# Adafruit_Metro_ESP32-S3_Rev_B.net
KiCad netlist of a schematic drawn in EAGLE
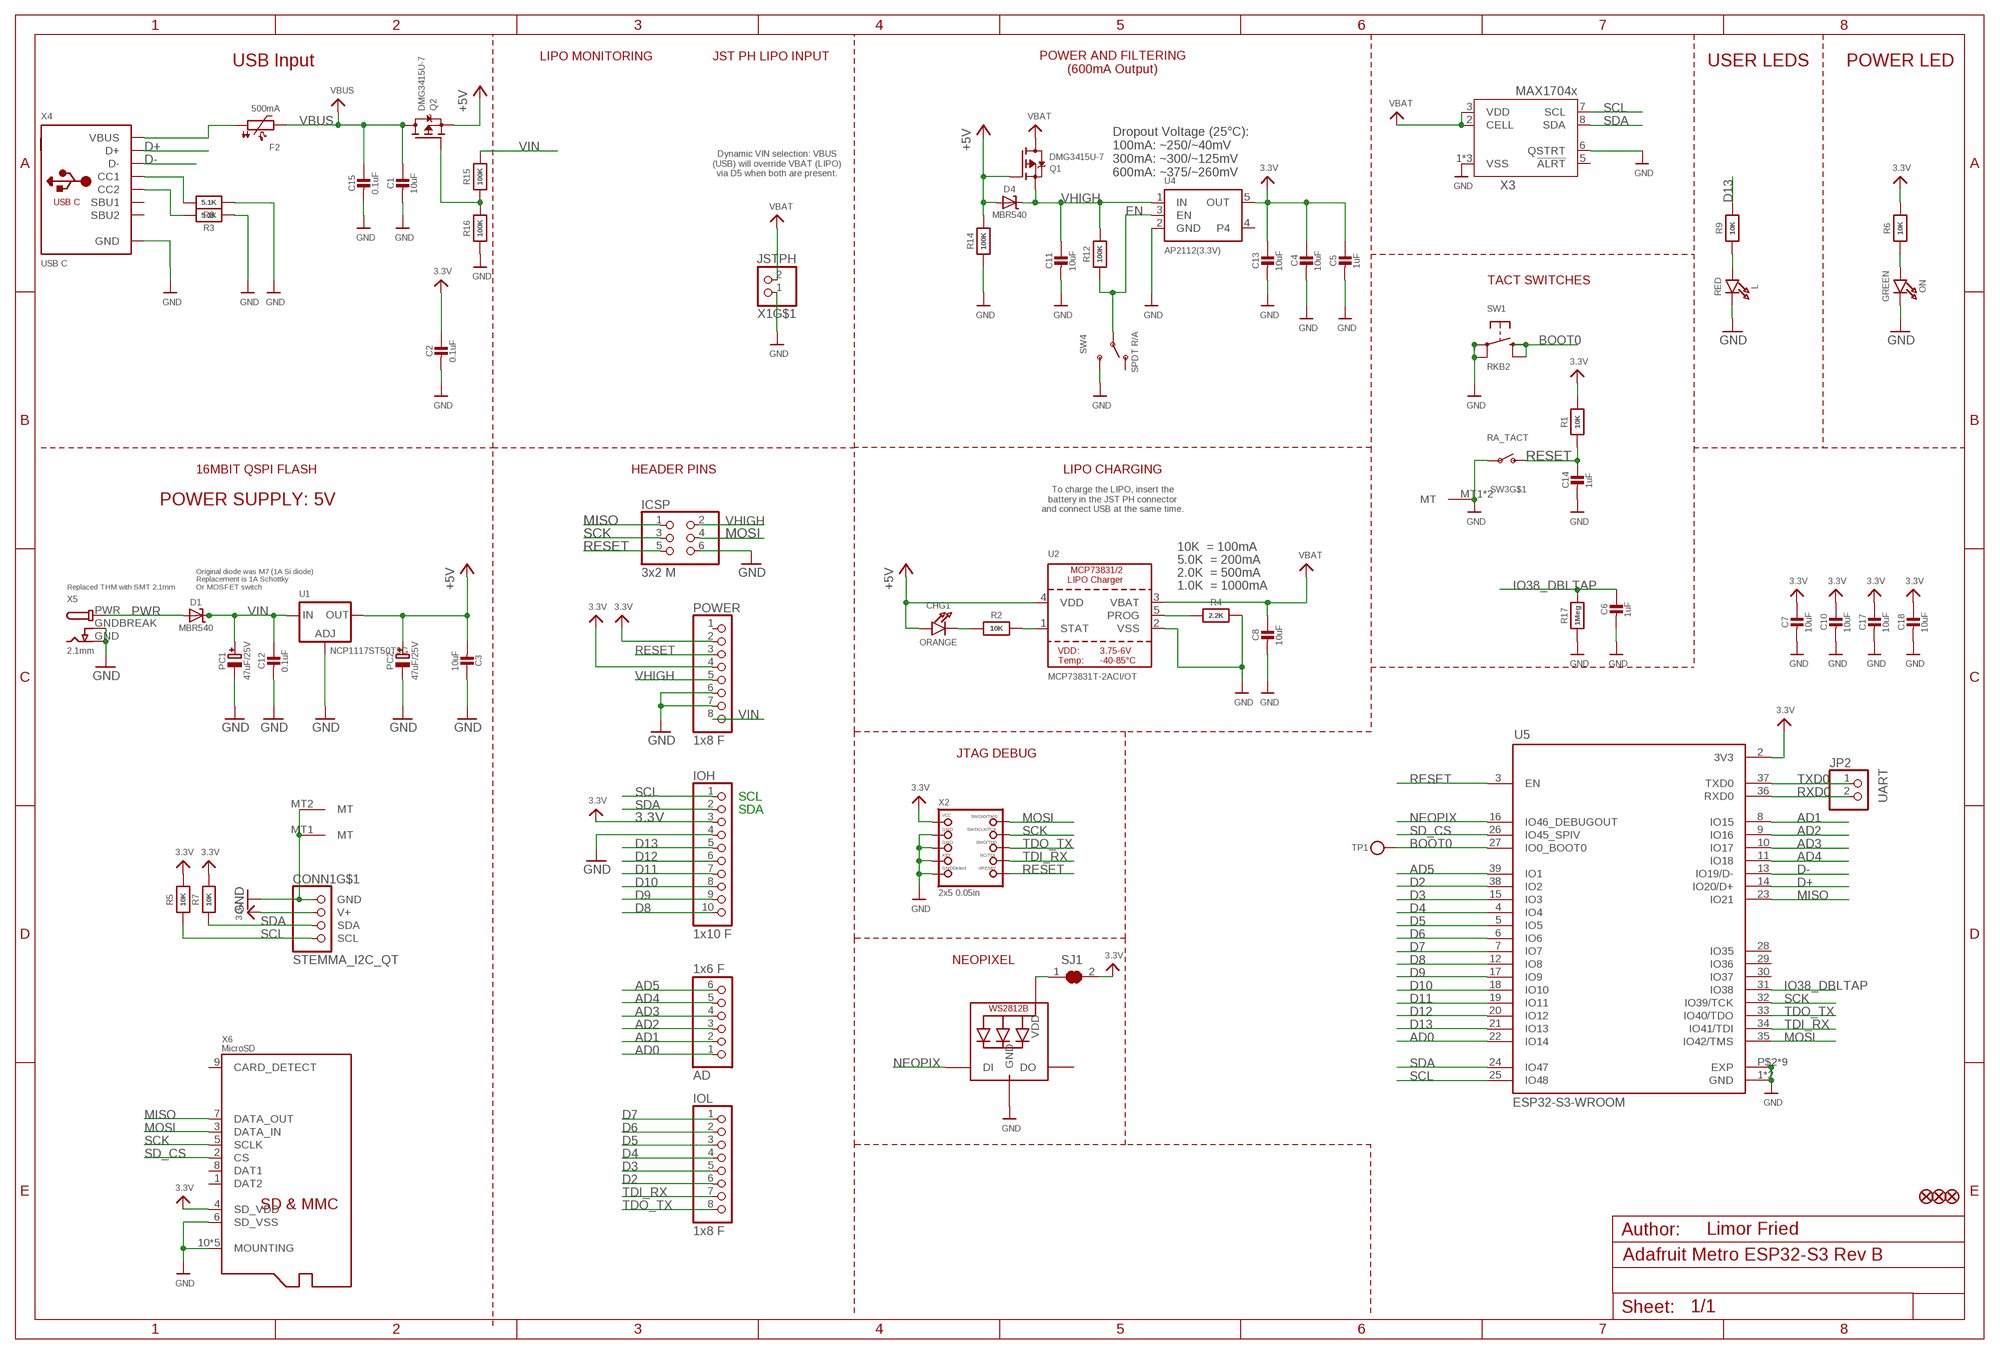
[diagram p0: schematic, sheet 1]

(export (version "E")
  (design (tool "Eeschema 10.0.6"))
  (components
    (comp (ref "AD")
      (value "1x6 F")
      (footprint "eagle-import:1X06_OVALWAVE")
      (libsource (lib "eagle-import") (part "HEADER-1X6OVALWAVE"))
    )
    (comp (ref "C1")
      (value "10uF")
      (footprint "eagle-import:0805-NO")
      (libsource (lib "eagle-import") (part "CAP_CERAMIC0805-NOOUTLINE"))
    )
    (comp (ref "C2")
      (value "0.1uF")
      (footprint "eagle-import:0603-NO")
      (libsource (lib "eagle-import") (part "CAP_CERAMIC0603_NO"))
    )
    (comp (ref "C3")
      (value "10uF")
      (footprint "eagle-import:0805-NO")
      (libsource (lib "eagle-import") (part "CAP_CERAMIC0805-NOOUTLINE"))
    )
    (comp (ref "C4")
      (value "10uF")
      (footprint "eagle-import:0805-NO")
      (libsource (lib "eagle-import") (part "CAP_CERAMIC0805-NOOUTLINE"))
    )
    (comp (ref "C5")
      (value "1uF")
      (footprint "eagle-import:0603-NO")
      (libsource (lib "eagle-import") (part "CAP_CERAMIC0603_NO"))
    )
    (comp (ref "C6")
      (value "1uF")
      (footprint "eagle-import:0603-NO")
      (libsource (lib "eagle-import") (part "CAP_CERAMIC0603_NO"))
    )
    (comp (ref "C7")
      (value "10uF")
      (footprint "eagle-import:0805-NO")
      (libsource (lib "eagle-import") (part "CAP_CERAMIC0805-NOOUTLINE"))
    )
    (comp (ref "C8")
      (value "10uF")
      (footprint "eagle-import:0805-NO")
      (libsource (lib "eagle-import") (part "CAP_CERAMIC0805-NOOUTLINE"))
    )
    (comp (ref "C10")
      (value "10uF")
      (footprint "eagle-import:0805-NO")
      (libsource (lib "eagle-import") (part "CAP_CERAMIC0805-NOOUTLINE"))
    )
    (comp (ref "C11")
      (value "10uF")
      (footprint "eagle-import:0805-NO")
      (libsource (lib "eagle-import") (part "CAP_CERAMIC0805-NOOUTLINE"))
    )
    (comp (ref "C12")
      (value "0.1uF")
      (footprint "eagle-import:0603-NO")
      (libsource (lib "eagle-import") (part "CAP_CERAMIC0603_NO"))
    )
    (comp (ref "C13")
      (value "10uF")
      (footprint "eagle-import:0805-NO")
      (libsource (lib "eagle-import") (part "CAP_CERAMIC0805-NOOUTLINE"))
    )
    (comp (ref "C14")
      (value "1uF")
      (footprint "eagle-import:0603-NO")
      (libsource (lib "eagle-import") (part "CAP_CERAMIC0603_NO"))
    )
    (comp (ref "C15")
      (value "0.1uF")
      (footprint "eagle-import:0603-NO")
      (libsource (lib "eagle-import") (part "CAP_CERAMIC0603_NO"))
    )
    (comp (ref "C17")
      (value "10uF")
      (footprint "eagle-import:0805-NO")
      (libsource (lib "eagle-import") (part "CAP_CERAMIC0805-NOOUTLINE"))
    )
    (comp (ref "C18")
      (value "10uF")
      (footprint "eagle-import:0805-NO")
      (libsource (lib "eagle-import") (part "CAP_CERAMIC0805-NOOUTLINE"))
    )
    (comp (ref "CHG1")
      (value "ORANGE")
      (footprint "eagle-import:CHIPLED_0603_NOOUTLINE")
      (libsource (lib "eagle-import") (part "LED0603_NOOUTLINE"))
    )
    (comp (ref "CONN1")
      (value "STEMMA_I2C_QT")
      (footprint "eagle-import:JST_SH4")
      (libsource (lib "eagle-import") (part "STEMMA_I2C_QT"))
    )
    (comp (ref "D1")
      (value "MBR540")
      (footprint "eagle-import:SOD-123")
      (libsource (lib "eagle-import") (part "DIODE-SCHOTTKYSOD-123"))
    )
    (comp (ref "D4")
      (value "MBR540")
      (footprint "eagle-import:SOD-123")
      (libsource (lib "eagle-import") (part "DIODE-SCHOTTKYSOD-123"))
    )
    (comp (ref "F2")
      (value "500mA")
      (footprint "eagle-import:0805-NO")
      (libsource (lib "eagle-import") (part "PTC_0805"))
    )
    (comp (ref "FD1")
      (value "FIDUCIAL_1MM")
      (footprint "eagle-import:FIDUCIAL_1MM")
      (libsource (lib "eagle-import") (part "FIDUCIAL_1MM"))
    )
    (comp (ref "FD2")
      (value "FIDUCIAL_1MM")
      (footprint "eagle-import:FIDUCIAL_1MM")
      (libsource (lib "eagle-import") (part "FIDUCIAL_1MM"))
    )
    (comp (ref "FD3")
      (value "FIDUCIAL_1MM")
      (footprint "eagle-import:FIDUCIAL_1MM")
      (libsource (lib "eagle-import") (part "FIDUCIAL_1MM"))
    )
    (comp (ref "ICSP")
      (value "3x2 M")
      (footprint "eagle-import:2X03_ROUND_70MIL")
      (libsource (lib "eagle-import") (part "HEADER-2X3"))
    )
    (comp (ref "IOH")
      (value "1x10 F")
      (footprint "eagle-import:1X10_OVALWAVE")
      (libsource (lib "eagle-import") (part "HEADER-1X10OVALWAVE"))
    )
    (comp (ref "IOL")
      (value "1x8 F")
      (footprint "eagle-import:1X08_OVALWAVE")
      (libsource (lib "eagle-import") (part "HEADER-1X8OVALWAVE"))
    )
    (comp (ref "JP2")
      (value "UART")
      (footprint "eagle-import:1X02_ROUND")
      (libsource (lib "eagle-import") (part "HEADER-1X2ROUND"))
    )
    (comp (ref "L")
      (value "RED")
      (footprint "eagle-import:CHIPLED_0603_NOOUTLINE")
      (libsource (lib "eagle-import") (part "LED0603_NOOUTLINE"))
    )
    (comp (ref "LED1")
      (value "WS2812B_3535FULL")
      (footprint "eagle-import:LED3535_FULLPADS")
      (libsource (lib "eagle-import") (part "WS2812B_3535FULL"))
    )
    (comp (ref "ON")
      (value "GREEN")
      (footprint "eagle-import:CHIPLED_0603_NOOUTLINE")
      (libsource (lib "eagle-import") (part "LED0603_NOOUTLINE"))
    )
    (comp (ref "PC1")
      (value "47uF/25V")
      (footprint "eagle-import:PANASONIC_D")
      (libsource (lib "eagle-import") (part "CAP_ELECTROLYTICPANASONIC_D"))
    )
    (comp (ref "PC2")
      (value "47uF/25V")
      (footprint "eagle-import:PANASONIC_D")
      (libsource (lib "eagle-import") (part "CAP_ELECTROLYTICPANASONIC_D"))
    )
    (comp (ref "POWER")
      (value "1x8 F")
      (footprint "eagle-import:1X08_OVALWAVE")
      (libsource (lib "eagle-import") (part "HEADER-1X8OVALWAVE"))
    )
    (comp (ref "Q1")
      (value "DMG3415U-7")
      (footprint "eagle-import:SOT23-R")
      (libsource (lib "eagle-import") (part "MOSFET-P"))
    )
    (comp (ref "Q2")
      (value "DMG3415U-7")
      (footprint "eagle-import:SOT23-R")
      (libsource (lib "eagle-import") (part "MOSFET-P"))
    )
    (comp (ref "R1")
      (value "10K")
      (footprint "eagle-import:0603-NO")
      (libsource (lib "eagle-import") (part "RESISTOR_0603_NOOUT"))
    )
    (comp (ref "R2")
      (value "10K")
      (footprint "eagle-import:0603-NO")
      (libsource (lib "eagle-import") (part "RESISTOR_0603_NOOUT"))
    )
    (comp (ref "R3")
      (value "5.1K")
      (footprint "eagle-import:0603-NO")
      (libsource (lib "eagle-import") (part "RESISTOR_0603_NOOUT"))
    )
    (comp (ref "R4")
      (value "2.2K")
      (footprint "eagle-import:0603-NO")
      (libsource (lib "eagle-import") (part "RESISTOR_0603_NOOUT"))
    )
    (comp (ref "R5")
      (value "10K")
      (footprint "eagle-import:0603-NO")
      (libsource (lib "eagle-import") (part "RESISTOR_0603_NOOUT"))
    )
    (comp (ref "R6")
      (value "10K")
      (footprint "eagle-import:0603-NO")
      (libsource (lib "eagle-import") (part "RESISTOR_0603_NOOUT"))
    )
    (comp (ref "R7")
      (value "10K")
      (footprint "eagle-import:0603-NO")
      (libsource (lib "eagle-import") (part "RESISTOR_0603_NOOUT"))
    )
    (comp (ref "R8")
      (value "5.1K")
      (footprint "eagle-import:0603-NO")
      (libsource (lib "eagle-import") (part "RESISTOR_0603_NOOUT"))
    )
    (comp (ref "R9")
      (value "10K")
      (footprint "eagle-import:0603-NO")
      (libsource (lib "eagle-import") (part "RESISTOR_0603_NOOUT"))
    )
    (comp (ref "R12")
      (value "100K")
      (footprint "eagle-import:0603-NO")
      (libsource (lib "eagle-import") (part "RESISTOR_0603_NOOUT"))
    )
    (comp (ref "R14")
      (value "100K")
      (footprint "eagle-import:0603-NO")
      (libsource (lib "eagle-import") (part "RESISTOR_0603_NOOUT"))
    )
    (comp (ref "R15")
      (value "100K")
      (footprint "eagle-import:0603-NO")
      (libsource (lib "eagle-import") (part "RESISTOR_0603_NOOUT"))
    )
    (comp (ref "R16")
      (value "100K")
      (footprint "eagle-import:0603-NO")
      (libsource (lib "eagle-import") (part "RESISTOR_0603_NOOUT"))
    )
    (comp (ref "R17")
      (value "1Meg")
      (footprint "eagle-import:0603-NO")
      (libsource (lib "eagle-import") (part "RESISTOR_0603_NOOUT"))
    )
    (comp (ref "SJ1")
      (value "SOLDERJUMPER_CLOSED")
      (footprint "eagle-import:SOLDERJUMPER_CLOSEDWIRE")
      (libsource (lib "eagle-import") (part "SOLDERJUMPER_CLOSED"))
    )
    (comp (ref "SW1")
      (value "RKB2")
      (footprint "eagle-import:BTN_RKB2_4.6X2.8")
      (libsource (lib "eagle-import") (part "SWITCH_TACT_SMT_RKB2"))
    )
    (comp (ref "SW3")
      (value "RA_TACT")
      (footprint "eagle-import:SPST_TACTILE_RA")
      (libsource (lib "eagle-import") (part "SWITCH_SPST_MNT_TACT_RA"))
    )
    (comp (ref "SW4")
      (value "SPDT R/A")
      (footprint "eagle-import:SPDT_SMT_SSSS811101")
      (libsource (lib "eagle-import") (part "SWITCH_SPDT"))
    )
    (comp (ref "TP1")
      (value "TESTPOINTROUND1.5MMNO")
      (footprint "eagle-import:TESTPOINT_ROUND_1.5MM_NO")
      (libsource (lib "eagle-import") (part "TESTPOINTROUND1.5MMNO"))
    )
    (comp (ref "U1")
      (value "NCP1117ST50T3G")
      (footprint "eagle-import:SOT223-R")
      (libsource (lib "eagle-import") (part "LM1117SOT223-REFLOW"))
    )
    (comp (ref "U2")
      (value "MCP73831T-2ACI/OT")
      (footprint "eagle-import:SOT23-5")
      (libsource (lib "eagle-import") (part "MCP73831/2"))
    )
    (comp (ref "U4")
      (value "AP2112(3.3V)")
      (footprint "eagle-import:SOT23-5")
      (fields (field (name "JLC_ROTATION") "0"))
      (libsource (lib "eagle-import") (part "VREG_SOT23-5"))
    )
    (comp (ref "U5")
      (value "ESP32-S3-WROOM")
      (footprint "eagle-import:S3-WROOM32")
      (libsource (lib "eagle-import") (part "ESP32-S3-WROOM"))
    )
    (comp (ref "X1")
      (value "JSTPH")
      (footprint "eagle-import:JSTPH2_BATT")
      (libsource (lib "eagle-import") (part "CON_JST_PH_2PIN_MT_BATT"))
    )
    (comp (ref "X2")
      (value "2x5 0.05in")
      (footprint "eagle-import:2X05_1.27MM_BOX_POSTS")
      (libsource (lib "eagle-import") (part "JTAG-CORTEXBOXPOSTS"))
    )
    (comp (ref "X3")
      (value "MAX17048/T")
      (footprint "eagle-import:TDFN8_2X2MM")
      (libsource (lib "eagle-import") (part "MAX17048/T"))
    )
    (comp (ref "X4")
      (value "USB C")
      (footprint "eagle-import:USB_C_CUSB31-CFM2AX-01-X")
      (libsource (lib "eagle-import") (part "USB_C"))
    )
    (comp (ref "X5")
      (value "2.1mm")
      (footprint "eagle-import:DCJACK_2MM_PTH")
      (libsource (lib "eagle-import") (part "DCBARRELPTH"))
    )
    (comp (ref "X6")
      (value "MicroSD")
      (footprint "eagle-import:MOLEX_104031-0811")
      (libsource (lib "eagle-import") (part "MICROSD104031-0811"))
    )
  )
  (nets
    (net (code "1") (name "+5V") (class "Default")
      (node (ref "C3") (pin "2") (pinfunction "2_2") (pintype "passive"))
      (node (ref "CHG1") (pin "A") (pinfunction "A_A") (pintype "passive"))
      (node (ref "D4") (pin "A") (pinfunction "A_A") (pintype "passive"))
      (node (ref "PC2") (pin "+") (pinfunction "+_+") (pintype "passive"))
      (node (ref "Q1") (pin "1") (pinfunction "G_1") (pintype "passive"))
      (node (ref "Q2") (pin "2") (pinfunction "S_2") (pintype "passive"))
      (node (ref "R14") (pin "2") (pinfunction "2_2") (pintype "passive"))
      (node (ref "U1") (pin "2") (pinfunction "OUT_2") (pintype "passive"))
      (node (ref "U1") (pin "4") (pinfunction "OUT_4") (pintype "passive"))
      (node (ref "U2") (pin "4") (pinfunction "VDD_4") (pintype "power_in"))
    )
    (net (code "2") (name "/AD0") (class "Default")
      (node (ref "AD") (pin "1") (pinfunction "1_1") (pintype "passive"))
      (node (ref "U5") (pin "22") (pinfunction "IO14_22") (pintype "bidirectional"))
    )
    (net (code "3") (name "/AD1") (class "Default")
      (node (ref "AD") (pin "2") (pinfunction "2_2") (pintype "passive"))
      (node (ref "U5") (pin "8") (pinfunction "IO15_8") (pintype "bidirectional"))
    )
    (net (code "4") (name "/AD2") (class "Default")
      (node (ref "AD") (pin "3") (pinfunction "3_3") (pintype "passive"))
      (node (ref "U5") (pin "9") (pinfunction "IO16_9") (pintype "bidirectional"))
    )
    (net (code "5") (name "/AD3") (class "Default")
      (node (ref "AD") (pin "4") (pinfunction "4_4") (pintype "passive"))
      (node (ref "U5") (pin "10") (pinfunction "IO17_10") (pintype "bidirectional"))
    )
    (net (code "6") (name "/AD4") (class "Default")
      (node (ref "AD") (pin "5") (pinfunction "5_5") (pintype "passive"))
      (node (ref "U5") (pin "11") (pinfunction "IO18_11") (pintype "bidirectional"))
    )
    (net (code "7") (name "/AD5") (class "Default")
      (node (ref "AD") (pin "6") (pinfunction "6_6") (pintype "passive"))
      (node (ref "U5") (pin "39") (pinfunction "IO1_39") (pintype "bidirectional"))
    )
    (net (code "8") (name "/BOOT0") (class "Default")
      (node (ref "SW1") (pin "B") (pinfunction "S_B") (pintype "passive"))
      (node (ref "SW1") (pin "B'") (pinfunction "S1_B'") (pintype "passive"))
      (node (ref "TP1") (pin "P$1") (pinfunction "P$1_P$1") (pintype "bidirectional"))
      (node (ref "U5") (pin "27") (pinfunction "IO0_BOOT0_27") (pintype "bidirectional"))
    )
    (net (code "9") (name "/D+") (class "Default")
      (node (ref "U5") (pin "14") (pinfunction "IO20/D+_14") (pintype "bidirectional"))
      (node (ref "X4") (pin "A6") (pinfunction "D+_A6") (pintype "bidirectional"))
      (node (ref "X4") (pin "B6") (pinfunction "D+_B6") (pintype "bidirectional"))
    )
    (net (code "10") (name "/D-") (class "Default")
      (node (ref "U5") (pin "13") (pinfunction "IO19/D-_13") (pintype "bidirectional"))
      (node (ref "X4") (pin "A7") (pinfunction "D-_A7") (pintype "bidirectional"))
      (node (ref "X4") (pin "B7") (pinfunction "D-_B7") (pintype "bidirectional"))
    )
    (net (code "11") (name "/D2") (class "Default")
      (node (ref "IOL") (pin "6") (pinfunction "6_6") (pintype "passive"))
      (node (ref "U5") (pin "38") (pinfunction "IO2_38") (pintype "bidirectional"))
    )
    (net (code "12") (name "/D3") (class "Default")
      (node (ref "IOL") (pin "5") (pinfunction "5_5") (pintype "passive"))
      (node (ref "U5") (pin "15") (pinfunction "IO3_15") (pintype "bidirectional"))
    )
    (net (code "13") (name "/D4") (class "Default")
      (node (ref "IOL") (pin "4") (pinfunction "4_4") (pintype "passive"))
      (node (ref "U5") (pin "4") (pinfunction "IO4_4") (pintype "bidirectional"))
    )
    (net (code "14") (name "/D5") (class "Default")
      (node (ref "IOL") (pin "3") (pinfunction "3_3") (pintype "passive"))
      (node (ref "U5") (pin "5") (pinfunction "IO5_5") (pintype "bidirectional"))
    )
    (net (code "15") (name "/D6") (class "Default")
      (node (ref "IOL") (pin "2") (pinfunction "2_2") (pintype "passive"))
      (node (ref "U5") (pin "6") (pinfunction "IO6_6") (pintype "bidirectional"))
    )
    (net (code "16") (name "/D7") (class "Default")
      (node (ref "IOL") (pin "1") (pinfunction "1_1") (pintype "passive"))
      (node (ref "U5") (pin "7") (pinfunction "IO7_7") (pintype "bidirectional"))
    )
    (net (code "17") (name "/D8") (class "Default")
      (node (ref "IOH") (pin "10") (pinfunction "10_10") (pintype "passive"))
      (node (ref "U5") (pin "12") (pinfunction "IO8_12") (pintype "bidirectional"))
    )
    (net (code "18") (name "/D9") (class "Default")
      (node (ref "IOH") (pin "9") (pinfunction "9_9") (pintype "passive"))
      (node (ref "U5") (pin "17") (pinfunction "IO9_17") (pintype "bidirectional"))
    )
    (net (code "19") (name "/D10") (class "Default")
      (node (ref "IOH") (pin "8") (pinfunction "8_8") (pintype "passive"))
      (node (ref "U5") (pin "18") (pinfunction "IO10_18") (pintype "bidirectional"))
    )
    (net (code "20") (name "/D11") (class "Default")
      (node (ref "IOH") (pin "7") (pinfunction "7_7") (pintype "passive"))
      (node (ref "U5") (pin "19") (pinfunction "IO11_19") (pintype "bidirectional"))
    )
    (net (code "21") (name "/D12") (class "Default")
      (node (ref "IOH") (pin "6") (pinfunction "6_6") (pintype "passive"))
      (node (ref "U5") (pin "20") (pinfunction "IO12_20") (pintype "bidirectional"))
    )
    (net (code "22") (name "/D13") (class "Default")
      (node (ref "IOH") (pin "5") (pinfunction "5_5") (pintype "passive"))
      (node (ref "R9") (pin "2") (pinfunction "2_2") (pintype "passive"))
      (node (ref "U5") (pin "21") (pinfunction "IO13_21") (pintype "bidirectional"))
    )
    (net (code "23") (name "/EN") (class "Default")
      (node (ref "R12") (pin "1") (pinfunction "1_1") (pintype "passive"))
      (node (ref "SW4") (pin "B") (pinfunction "P_B") (pintype "passive"))
      (node (ref "U4") (pin "3") (pinfunction "EN_3") (pintype "input"))
    )
    (net (code "24") (name "/IO38_DBLTAP") (class "Default")
      (node (ref "C6") (pin "1") (pinfunction "1_1") (pintype "passive"))
      (node (ref "R17") (pin "2") (pinfunction "2_2") (pintype "passive"))
      (node (ref "U5") (pin "31") (pinfunction "IO38_31") (pintype "bidirectional"))
    )
    (net (code "25") (name "/MISO") (class "Default")
      (node (ref "ICSP") (pin "1") (pinfunction "1_1") (pintype "passive"))
      (node (ref "U5") (pin "23") (pinfunction "IO21_23") (pintype "bidirectional"))
      (node (ref "X6") (pin "7") (pinfunction "DATA_OUT_7") (pintype "output"))
    )
    (net (code "26") (name "/MOSI") (class "Default")
      (node (ref "ICSP") (pin "4") (pinfunction "4_4") (pintype "passive"))
      (node (ref "U5") (pin "35") (pinfunction "IO42/TMS_35") (pintype "bidirectional"))
      (node (ref "X2") (pin "2") (pinfunction "SWDIO_2") (pintype "bidirectional"))
      (node (ref "X6") (pin "3") (pinfunction "DATA_IN_3") (pintype "input"))
    )
    (net (code "27") (name "/NEOPIX") (class "Default")
      (node (ref "LED1") (pin "1") (pinfunction "DI_1") (pintype "input"))
      (node (ref "U5") (pin "16") (pinfunction "IO46_DEBUGOUT_16") (pintype "input"))
    )
    (net (code "28") (name "/PWR") (class "Default")
      (node (ref "D1") (pin "A") (pinfunction "A_A") (pintype "passive"))
      (node (ref "X5") (pin "PWR") (pinfunction "PWR_PWR") (pintype "power_in"))
    )
    (net (code "29") (name "/RESET") (class "Default")
      (node (ref "C14") (pin "1") (pinfunction "1_1") (pintype "passive"))
      (node (ref "ICSP") (pin "5") (pinfunction "5_5") (pintype "passive"))
      (node (ref "POWER") (pin "3") (pinfunction "3_3") (pintype "passive"))
      (node (ref "R1") (pin "1") (pinfunction "1_1") (pintype "passive"))
      (node (ref "SW3") (pin "2") (pinfunction "S_2") (pintype "passive"))
      (node (ref "U5") (pin "3") (pinfunction "EN_3") (pintype "input"))
      (node (ref "X2") (pin "10") (pinfunction "NRESET_10") (pintype "bidirectional"))
    )
    (net (code "30") (name "/RXD0") (class "Default")
      (node (ref "JP2") (pin "2") (pinfunction "2_2") (pintype "passive"))
      (node (ref "U5") (pin "36") (pinfunction "RXD0_36") (pintype "bidirectional"))
    )
    (net (code "31") (name "/SCK") (class "Default")
      (node (ref "ICSP") (pin "3") (pinfunction "3_3") (pintype "passive"))
      (node (ref "U5") (pin "32") (pinfunction "IO39/TCK_32") (pintype "bidirectional"))
      (node (ref "X2") (pin "4") (pinfunction "SWDCLK_4") (pintype "bidirectional"))
      (node (ref "X6") (pin "5") (pinfunction "SCLK_5") (pintype "input"))
    )
    (net (code "32") (name "/SCL") (class "Default")
      (node (ref "CONN1") (pin "4") (pinfunction "SCL_4") (pintype "passive"))
      (node (ref "IOH") (pin "1") (pinfunction "1_1") (pintype "passive"))
      (node (ref "R5") (pin "1") (pinfunction "1_1") (pintype "passive"))
      (node (ref "U5") (pin "25") (pinfunction "IO48_25") (pintype "input"))
      (node (ref "X3") (pin "7") (pinfunction "SCL_7") (pintype "bidirectional"))
    )
    (net (code "33") (name "/SDA") (class "Default")
      (node (ref "CONN1") (pin "3") (pinfunction "SDA_3") (pintype "passive"))
      (node (ref "IOH") (pin "2") (pinfunction "2_2") (pintype "passive"))
      (node (ref "R7") (pin "1") (pinfunction "1_1") (pintype "passive"))
      (node (ref "U5") (pin "24") (pinfunction "IO47_24") (pintype "bidirectional"))
      (node (ref "X3") (pin "8") (pinfunction "SDA_8") (pintype "bidirectional"))
    )
    (net (code "34") (name "/SD_CS") (class "Default")
      (node (ref "U5") (pin "26") (pinfunction "IO45_SPIV_26") (pintype "bidirectional"))
      (node (ref "X6") (pin "2") (pinfunction "CS_2") (pintype "input"))
    )
    (net (code "35") (name "/TDI_RX") (class "Default")
      (node (ref "IOL") (pin "7") (pinfunction "7_7") (pintype "passive"))
      (node (ref "U5") (pin "34") (pinfunction "IO41/TDI_34") (pintype "bidirectional"))
      (node (ref "X2") (pin "8") (pinfunction "TDI_8") (pintype "bidirectional"))
    )
    (net (code "36") (name "/TDO_TX") (class "Default")
      (node (ref "IOL") (pin "8") (pinfunction "8_8") (pintype "passive"))
      (node (ref "U5") (pin "33") (pinfunction "IO40/TDO_33") (pintype "bidirectional"))
      (node (ref "X2") (pin "6") (pinfunction "SWO_6") (pintype "bidirectional"))
    )
    (net (code "37") (name "/TXD0") (class "Default")
      (node (ref "JP2") (pin "1") (pinfunction "1_1") (pintype "passive"))
      (node (ref "U5") (pin "37") (pinfunction "TXD0_37") (pintype "bidirectional"))
    )
    (net (code "38") (name "/VHIGH") (class "Default")
      (node (ref "C11") (pin "1") (pinfunction "1_1") (pintype "passive"))
      (node (ref "D4") (pin "C") (pinfunction "C_C") (pintype "passive"))
      (node (ref "ICSP") (pin "2") (pinfunction "2_2") (pintype "passive"))
      (node (ref "POWER") (pin "5") (pinfunction "5_5") (pintype "passive"))
      (node (ref "Q1") (pin "2") (pinfunction "S_2") (pintype "passive"))
      (node (ref "R12") (pin "2") (pinfunction "2_2") (pintype "passive"))
      (node (ref "U4") (pin "1") (pinfunction "IN_1") (pintype "power_in"))
    )
    (net (code "39") (name "/VIN") (class "Default")
      (node (ref "C12") (pin "1") (pinfunction "1_1") (pintype "passive"))
      (node (ref "D1") (pin "C") (pinfunction "C_C") (pintype "passive"))
      (node (ref "PC1") (pin "+") (pinfunction "+_+") (pintype "passive"))
      (node (ref "POWER") (pin "8") (pinfunction "8_8") (pintype "passive"))
      (node (ref "R15") (pin "2") (pinfunction "2_2") (pintype "passive"))
      (node (ref "U1") (pin "3") (pinfunction "IN_3") (pintype "input"))
    )
    (net (code "40") (name "3.3V") (class "Default")
      (node (ref "C10") (pin "1") (pinfunction "1_1") (pintype "passive"))
      (node (ref "C13") (pin "1") (pinfunction "1_1") (pintype "passive"))
      (node (ref "C17") (pin "1") (pinfunction "1_1") (pintype "passive"))
      (node (ref "C18") (pin "1") (pinfunction "1_1") (pintype "passive"))
      (node (ref "C2") (pin "1") (pinfunction "1_1") (pintype "passive"))
      (node (ref "C4") (pin "1") (pinfunction "1_1") (pintype "passive"))
      (node (ref "C5") (pin "1") (pinfunction "1_1") (pintype "passive"))
      (node (ref "C7") (pin "1") (pinfunction "1_1") (pintype "passive"))
      (node (ref "CONN1") (pin "2") (pinfunction "V+_2") (pintype "passive"))
      (node (ref "IOH") (pin "3") (pinfunction "3_3") (pintype "passive"))
      (node (ref "POWER") (pin "2") (pinfunction "2_2") (pintype "passive"))
      (node (ref "POWER") (pin "4") (pinfunction "4_4") (pintype "passive"))
      (node (ref "R1") (pin "2") (pinfunction "2_2") (pintype "passive"))
      (node (ref "R5") (pin "2") (pinfunction "2_2") (pintype "passive"))
      (node (ref "R6") (pin "2") (pinfunction "2_2") (pintype "passive"))
      (node (ref "R7") (pin "2") (pinfunction "2_2") (pintype "passive"))
      (node (ref "SJ1") (pin "2") (pinfunction "2_2") (pintype "passive"))
      (node (ref "U4") (pin "5") (pinfunction "OUT_5") (pintype "power_in"))
      (node (ref "U5") (pin "2") (pinfunction "3V3_2") (pintype "power_in"))
      (node (ref "X2") (pin "1") (pinfunction "VCC_1") (pintype "power_in"))
      (node (ref "X6") (pin "4") (pinfunction "SD_VDD_4") (pintype "power_in"))
    )
    (net (code "41") (name "GND") (class "Default")
      (node (ref "C1") (pin "2") (pinfunction "2_2") (pintype "passive"))
      (node (ref "C10") (pin "2") (pinfunction "2_2") (pintype "passive"))
      (node (ref "C11") (pin "2") (pinfunction "2_2") (pintype "passive"))
      (node (ref "C12") (pin "2") (pinfunction "2_2") (pintype "passive"))
      (node (ref "C13") (pin "2") (pinfunction "2_2") (pintype "passive"))
      (node (ref "C14") (pin "2") (pinfunction "2_2") (pintype "passive"))
      (node (ref "C15") (pin "2") (pinfunction "2_2") (pintype "passive"))
      (node (ref "C17") (pin "2") (pinfunction "2_2") (pintype "passive"))
      (node (ref "C18") (pin "2") (pinfunction "2_2") (pintype "passive"))
      (node (ref "C2") (pin "2") (pinfunction "2_2") (pintype "passive"))
      (node (ref "C3") (pin "1") (pinfunction "1_1") (pintype "passive"))
      (node (ref "C4") (pin "2") (pinfunction "2_2") (pintype "passive"))
      (node (ref "C5") (pin "2") (pinfunction "2_2") (pintype "passive"))
      (node (ref "C6") (pin "2") (pinfunction "2_2") (pintype "passive"))
      (node (ref "C7") (pin "2") (pinfunction "2_2") (pintype "passive"))
      (node (ref "C8") (pin "2") (pinfunction "2_2") (pintype "passive"))
      (node (ref "CONN1") (pin "1") (pinfunction "GND_1") (pintype "passive"))
      (node (ref "CONN1") (pin "MT1") (pinfunction "MT_MT1") (pintype "bidirectional"))
      (node (ref "CONN1") (pin "MT2") (pinfunction "MT_MT2") (pintype "bidirectional"))
      (node (ref "ICSP") (pin "6") (pinfunction "6_6") (pintype "passive"))
      (node (ref "IOH") (pin "4") (pinfunction "4_4") (pintype "passive"))
      (node (ref "L") (pin "C") (pinfunction "C_C") (pintype "passive"))
      (node (ref "LED1") (pin "4") (pinfunction "GND_4") (pintype "power_in"))
      (node (ref "ON") (pin "C") (pinfunction "C_C") (pintype "passive"))
      (node (ref "PC1") (pin "-") (pinfunction "-_-") (pintype "passive"))
      (node (ref "PC2") (pin "-") (pinfunction "-_-") (pintype "passive"))
      (node (ref "POWER") (pin "6") (pinfunction "6_6") (pintype "passive"))
      (node (ref "POWER") (pin "7") (pinfunction "7_7") (pintype "passive"))
      (node (ref "R14") (pin "1") (pinfunction "1_1") (pintype "passive"))
      (node (ref "R16") (pin "1") (pinfunction "1_1") (pintype "passive"))
      (node (ref "R17") (pin "1") (pinfunction "1_1") (pintype "passive"))
      (node (ref "R3") (pin "1") (pinfunction "1_1") (pintype "passive"))
      (node (ref "R4") (pin "2") (pinfunction "2_2") (pintype "passive"))
      (node (ref "R8") (pin "1") (pinfunction "1_1") (pintype "passive"))
      (node (ref "SW1") (pin "A") (pinfunction "P_A") (pintype "passive"))
      (node (ref "SW1") (pin "A'") (pinfunction "P1_A'") (pintype "passive"))
      (node (ref "SW3") (pin "1") (pinfunction "P_1") (pintype "passive"))
      (node (ref "SW3") (pin "MT1") (pinfunction "MT_MT1") (pintype "bidirectional"))
      (node (ref "SW3") (pin "MT2") (pinfunction "MT_MT2") (pintype "bidirectional"))
      (node (ref "SW4") (pin "C") (pinfunction "S_C") (pintype "passive"))
      (node (ref "U1") (pin "1") (pinfunction "ADJ_1") (pintype "input"))
      (node (ref "U2") (pin "2") (pinfunction "VSS_2") (pintype "power_in"))
      (node (ref "U4") (pin "2") (pinfunction "GND_2") (pintype "power_in"))
      (node (ref "U5") (pin "1") (pinfunction "GND_1") (pintype "power_in"))
      (node (ref "U5") (pin "40") (pinfunction "GND_40") (pintype "power_in"))
      (node (ref "U5") (pin "P$10") (pinfunction "EXP_P$10") (pintype "power_in"))
      (node (ref "U5") (pin "P$2") (pinfunction "EXP_P$2") (pintype "power_in"))
      (node (ref "U5") (pin "P$3") (pinfunction "EXP_P$3") (pintype "power_in"))
      (node (ref "U5") (pin "P$4") (pinfunction "EXP_P$4") (pintype "power_in"))
      (node (ref "U5") (pin "P$5") (pinfunction "EXP_P$5") (pintype "power_in"))
      (node (ref "U5") (pin "P$6") (pinfunction "EXP_P$6") (pintype "power_in"))
      (node (ref "U5") (pin "P$7") (pinfunction "EXP_P$7") (pintype "power_in"))
      (node (ref "U5") (pin "P$8") (pinfunction "EXP_P$8") (pintype "power_in"))
      (node (ref "U5") (pin "P$9") (pinfunction "EXP_P$9") (pintype "power_in"))
      (node (ref "X1") (pin "1") (pinfunction "1_1") (pintype "passive"))
      (node (ref "X2") (pin "3") (pinfunction "GND_3") (pintype "power_in"))
      (node (ref "X2") (pin "5") (pinfunction "GND_5") (pintype "power_in"))
      (node (ref "X2") (pin "7") (pinfunction "KEY_7") (pintype "bidirectional"))
      (node (ref "X2") (pin "9") (pinfunction "GNDDETECT_9") (pintype "bidirectional"))
      (node (ref "X3") (pin "1") (pinfunction "VSS_1") (pintype "power_in"))
      (node (ref "X3") (pin "4") (pinfunction "VSS_4") (pintype "power_in"))
      (node (ref "X3") (pin "6") (pinfunction "QSTRT_6") (pintype "input"))
      (node (ref "X3") (pin "THERMAL") (pinfunction "VSS_THERMAL") (pintype "power_in"))
      (node (ref "X4") (pin "A1B12") (pinfunction "GND_A1B12") (pintype "power_in"))
      (node (ref "X4") (pin "B1A12") (pinfunction "GND_B1A12") (pintype "power_in"))
      (node (ref "X5") (pin "GND") (pinfunction "GND_GND") (pintype "power_in"))
      (node (ref "X5") (pin "GNDBREAK") (pinfunction "GNDBREAK_GNDBREAK") (pintype "power_in"))
      (node (ref "X6") (pin "10") (pinfunction "MOUNTING_10") (pintype "passive"))
      (node (ref "X6") (pin "6") (pinfunction "SD_VSS_6") (pintype "power_in"))
      (node (ref "X6") (pin "G1") (pinfunction "MOUNTING_G1") (pintype "passive"))
      (node (ref "X6") (pin "G2") (pinfunction "MOUNTING_G2") (pintype "passive"))
      (node (ref "X6") (pin "G3") (pinfunction "MOUNTING_G3") (pintype "passive"))
      (node (ref "X6") (pin "G4") (pinfunction "MOUNTING_G4") (pintype "passive"))
    )
    (net (code "42") (name "Net-(CHG1-PadC)") (class "Default")
      (node (ref "CHG1") (pin "C") (pinfunction "C_C") (pintype "passive"))
      (node (ref "R2") (pin "1") (pinfunction "1_1") (pintype "passive"))
    )
    (net (code "43") (name "Net-(F2-Pad1)") (class "Default")
      (node (ref "F2") (pin "1") (pinfunction "1_1") (pintype "passive"))
      (node (ref "X4") (pin "A4B9") (pinfunction "VBUS_A4B9") (pintype "power_in"))
      (node (ref "X4") (pin "B4A9") (pinfunction "VBUS_B4A9") (pintype "power_in"))
    )
    (net (code "44") (name "Net-(L-PadA)") (class "Default")
      (node (ref "L") (pin "A") (pinfunction "A_A") (pintype "passive"))
      (node (ref "R9") (pin "1") (pinfunction "1_1") (pintype "passive"))
    )
    (net (code "45") (name "Net-(LED1-VDD)") (class "Default")
      (node (ref "LED1") (pin "2") (pinfunction "VDD_2") (pintype "power_in"))
      (node (ref "SJ1") (pin "1") (pinfunction "1_1") (pintype "passive"))
    )
    (net (code "46") (name "Net-(ON-PadA)") (class "Default")
      (node (ref "ON") (pin "A") (pinfunction "A_A") (pintype "passive"))
      (node (ref "R6") (pin "1") (pinfunction "1_1") (pintype "passive"))
    )
    (net (code "47") (name "Net-(Q2-G)") (class "Default")
      (node (ref "Q2") (pin "1") (pinfunction "G_1") (pintype "passive"))
      (node (ref "R15") (pin "1") (pinfunction "1_1") (pintype "passive"))
      (node (ref "R16") (pin "2") (pinfunction "2_2") (pintype "passive"))
    )
    (net (code "48") (name "Net-(U2-PROG)") (class "Default")
      (node (ref "R4") (pin "1") (pinfunction "1_1") (pintype "passive"))
      (node (ref "U2") (pin "5") (pinfunction "PROG_5") (pintype "input"))
    )
    (net (code "49") (name "Net-(U2-STAT)") (class "Default")
      (node (ref "R2") (pin "2") (pinfunction "2_2") (pintype "passive"))
      (node (ref "U2") (pin "1") (pinfunction "STAT_1") (pintype "output"))
    )
    (net (code "50") (name "Net-(X4-CC1)") (class "Default")
      (node (ref "R8") (pin "2") (pinfunction "2_2") (pintype "passive"))
      (node (ref "X4") (pin "A5") (pinfunction "CC1_A5") (pintype "bidirectional"))
    )
    (net (code "51") (name "Net-(X4-CC2)") (class "Default")
      (node (ref "R3") (pin "2") (pinfunction "2_2") (pintype "passive"))
      (node (ref "X4") (pin "B5") (pinfunction "CC2_B5") (pintype "bidirectional"))
    )
    (net (code "52") (name "VBAT") (class "Default")
      (node (ref "C8") (pin "1") (pinfunction "1_1") (pintype "passive"))
      (node (ref "Q1") (pin "3") (pinfunction "D_3") (pintype "passive"))
      (node (ref "U2") (pin "3") (pinfunction "VBAT_3") (pintype "power_in"))
      (node (ref "X1") (pin "2") (pinfunction "2_2") (pintype "passive"))
      (node (ref "X3") (pin "2") (pinfunction "CELL_2") (pintype "power_in"))
      (node (ref "X3") (pin "3") (pinfunction "VDD_3") (pintype "power_in"))
    )
    (net (code "53") (name "VBUS") (class "Default")
      (node (ref "C1") (pin "1") (pinfunction "1_1") (pintype "passive"))
      (node (ref "C15") (pin "1") (pinfunction "1_1") (pintype "passive"))
      (node (ref "F2") (pin "2") (pinfunction "2_2") (pintype "passive"))
      (node (ref "Q2") (pin "3") (pinfunction "D_3") (pintype "passive"))
    )
    (net (code "54") (name "unconnected-(LED1-DO-Pad3)") (class "Default")
      (node (ref "LED1") (pin "3") (pinfunction "DO_3") (pintype "output"))
    )
    (net (code "55") (name "unconnected-(POWER-Pad1)") (class "Default")
      (node (ref "POWER") (pin "1") (pinfunction "1_1") (pintype "passive"))
    )
    (net (code "56") (name "unconnected-(SW4-O-PadA)") (class "Default")
      (node (ref "SW4") (pin "A") (pinfunction "O_A") (pintype "passive"))
    )
    (net (code "57") (name "unconnected-(U4-P4-Pad4)") (class "Default")
      (node (ref "U4") (pin "4") (pinfunction "P4_4") (pintype "bidirectional"))
    )
    (net (code "58") (name "unconnected-(U5-IO35-Pad28)") (class "Default")
      (node (ref "U5") (pin "28") (pinfunction "IO35_28") (pintype "input"))
    )
    (net (code "59") (name "unconnected-(U5-IO36-Pad29)") (class "Default")
      (node (ref "U5") (pin "29") (pinfunction "IO36_29") (pintype "bidirectional"))
    )
    (net (code "60") (name "unconnected-(U5-IO37-Pad30)") (class "Default")
      (node (ref "U5") (pin "30") (pinfunction "IO37_30") (pintype "bidirectional"))
    )
    (net (code "61") (name "unconnected-(X3-~{ALRT}-Pad5)") (class "Default")
      (node (ref "X3") (pin "5") (pinfunction "~{ALRT}_5") (pintype "output"))
    )
    (net (code "62") (name "unconnected-(X4-SBU1-PadA8)") (class "Default")
      (node (ref "X4") (pin "A8") (pinfunction "SBU1_A8") (pintype "bidirectional"))
    )
    (net (code "63") (name "unconnected-(X4-SBU2-PadB8)") (class "Default")
      (node (ref "X4") (pin "B8") (pinfunction "SBU2_B8") (pintype "bidirectional"))
    )
    (net (code "64") (name "unconnected-(X6-CARD_DETECT-Pad9)") (class "Default")
      (node (ref "X6") (pin "9") (pinfunction "CARD_DETECT_9") (pintype "passive"))
    )
    (net (code "65") (name "unconnected-(X6-DAT1-Pad8)") (class "Default")
      (node (ref "X6") (pin "8") (pinfunction "DAT1_8") (pintype "bidirectional"))
    )
    (net (code "66") (name "unconnected-(X6-DAT2-Pad1)") (class "Default")
      (node (ref "X6") (pin "1") (pinfunction "DAT2_1") (pintype "bidirectional"))
    )
  )
)
